# DC_Power_Regulation.net
KiCad netlist of a schematic drawn in Altium Designer
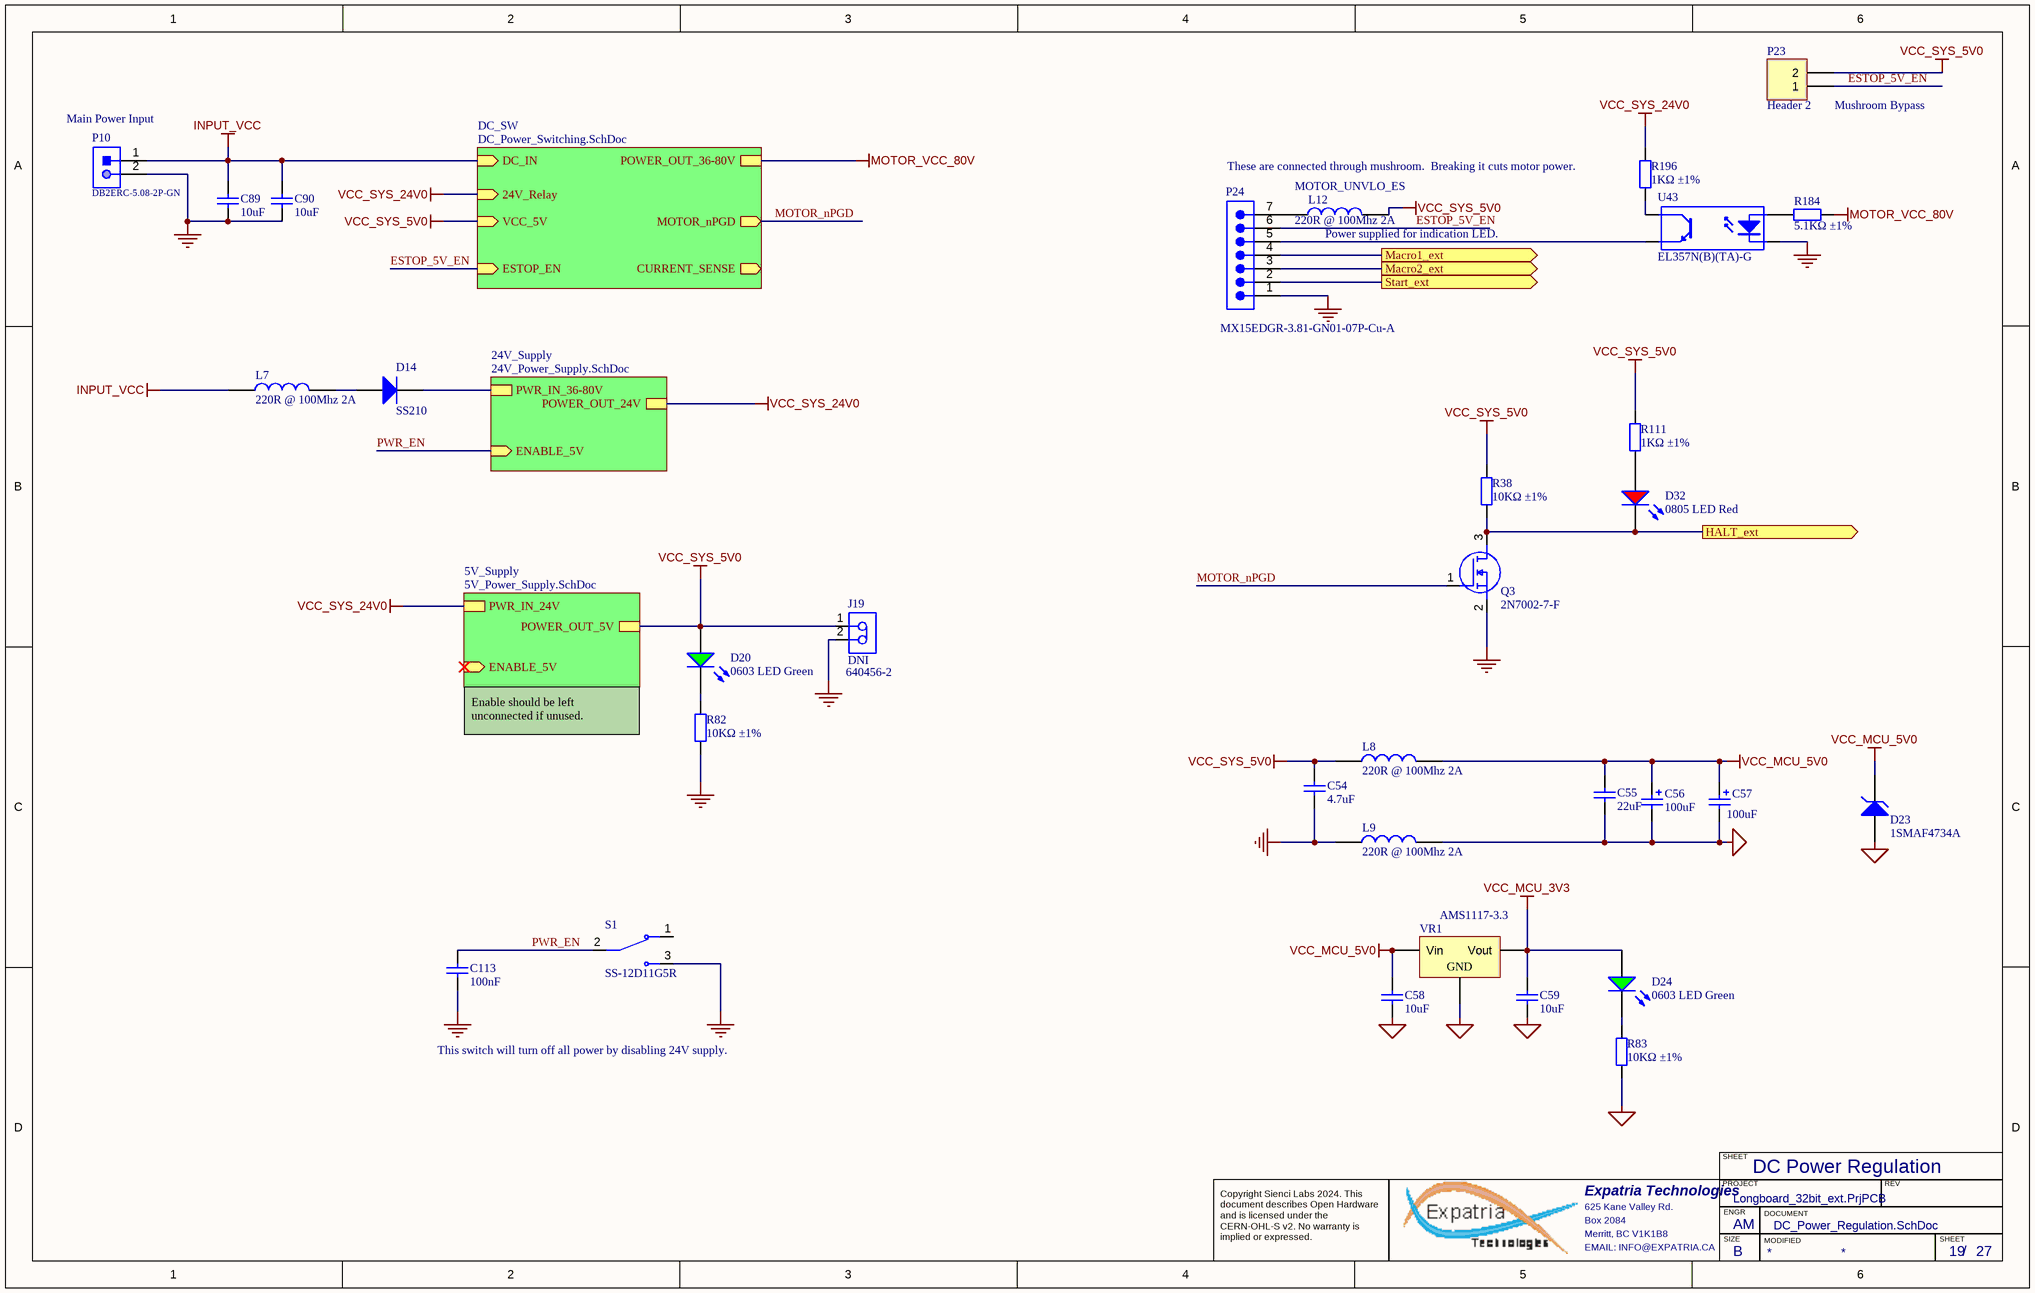
[diagram p0: DC_Power_Regulation.SchDoc]

(export (version "E")
  (design (tool "Eeschema 10.0.6"))
  (components
    (comp (ref "C54")
      (value "4.7uF")
      (footprint "0603_C")
      (description "16V 4.7uF X5R ±10% 0603 Multilayer Ceramic Capacitors MLCC - SMD/SMT ROHS")
      (fields (field (name "MANUFACTURER") "Samsung Electro-Mechanics") (field (name "TOLERANCE") "10%"))
      (libsource (lib "Sienci_Labs") (part "0603 4.7uF (475) 10% 16V"))
    )
    (comp (ref "C55")
      (value "22uF")
      (footprint "0805_C")
      (description "25V 22uF X5R ±20% 0805 Multilayer Ceramic Capacitors MLCC - SMD/SMT ROHS")
      (fields (field (name "MANUFACTURER") "Samsung Electro-Mechanics") (field (name "TOLERANCE") "20%"))
      (libsource (lib "Sienci_Labs") (part "0805 22uF (226) 20% 25V"))
    )
    (comp (ref "C56")
      (value "100uF")
      (footprint "CASE-B_3528")
      (description "Tantalum capacitor")
      (fields (field (name "MANUFACTURER") "AVX") (field (name "MANUFACTURER PART NUMBER") "TAJB107K006RNJ"))
      (libsource (lib "Cap") (part "3528 100uF (107) 10% 6.3V"))
    )
    (comp (ref "C57")
      (value "100uF")
      (footprint "WCAP-ASLI_D6.3H7.7")
      (fields
        (field (name "MANUFACTURER") "Capxon International Elec")
        (field (name "MANUFACTURER PART NUMBER") "HV101M035E077ETR")
      )
      (libsource (lib "IQAnalog") (part "865080445010"))
    )
    (comp (ref "C58")
      (value "10uF")
      (footprint "1206_C")
      (description "50V 10uF X5R ±10% 1206 Multilayer Ceramic Capacitors MLCC - SMD/SMT ROHS")
      (fields
        (field (name "MANUFACTURER") "Samsung Electro-Mechanics")
        (field (name "MANUFACTURER PART NUMBER") "CL31A106KBHNNNE")
      )
      (libsource (lib "Sienci_Labs") (part "1206 10uF (106) 10% 50V"))
    )
    (comp (ref "C59")
      (value "10uF")
      (footprint "1206_C")
      (description "50V 10uF X5R ±10% 1206 Multilayer Ceramic Capacitors MLCC - SMD/SMT ROHS")
      (fields
        (field (name "MANUFACTURER") "Samsung Electro-Mechanics")
        (field (name "MANUFACTURER PART NUMBER") "CL31A106KBHNNNE")
      )
      (libsource (lib "Sienci_Labs") (part "1206 10uF (106) 10% 50V"))
    )
    (comp (ref "C89")
      (value "10uF")
      (footprint "1206_C")
      (description "50V 10uF X5R ±10% 1206 Multilayer Ceramic Capacitors MLCC - SMD/SMT ROHS")
      (fields (field (name "MANUFACTURER") "Samsung Electro-Mechanics") (field (name "TOLERANCE") "10%"))
      (libsource (lib "Sienci_Labs") (part "1206 10uF (106) 10% 50V"))
    )
    (comp (ref "C90")
      (value "10uF")
      (footprint "1206_C")
      (description "50V 10uF X5R ±10% 1206 Multilayer Ceramic Capacitors MLCC - SMD/SMT ROHS")
      (fields (field (name "MANUFACTURER") "Samsung Electro-Mechanics") (field (name "TOLERANCE") "10%"))
      (libsource (lib "Sienci_Labs") (part "1206 10uF (106) 10% 50V"))
    )
    (comp (ref "C113")
      (value "100nF")
      (footprint "0603_C")
      (description "50V 100nF X7R ±10% 0603 Multilayer Ceramic Capacitors MLCC - SMD/SMT ROHS")
      (fields (field (name "MANUFACTURER") "YAGEO") (field (name "TOLERANCE") "10%"))
      (libsource (lib "Sienci_Labs") (part "0603 100nF (104) 10% 50V"))
    )
    (comp (ref "D14")
      (value "SS210")
      (footprint "SMA(DO-214AC)_S1")
      (description "100V 2A 850mV @ 2A SMA(DO-214AC) Schottky Barrier Diodes (SBD) ROHS")
      (fields (field (name "MANUFACTURER") "MDD(Microdiode Electronics)"))
      (libsource (lib "Diode") (part "SMA(DO-214AC) SS210"))
    )
    (comp (ref "D20")
      (value "0603 LED Green")
      (footprint "0603_LED_S1 - GREEN")
      (description "20mA -40℃~+85℃ 515nm~530nm Emerald 120° 60mW 0603 Light Emitting Diodes (LED) ROHS")
      (fields (field (name "MANUFACTURER PART NUMBER") "MHT192UGCT") (field (name "MANUFACTURER") "MEIHUA"))
      (libsource (lib "Sienci_Labs") (part "MHT192UGCT"))
    )
    (comp (ref "D23")
      (value "1SMAF4734A")
      (footprint "DIOM5226X240N")
      (description "27V ±5% 1W 500nA @ 20.5V SMA(DO-214AC) Zener Diodes RoHS")
      (fields (field (name "MANUFACTURER") "Shandong Jingdao Microelectronics"))
      (libsource (lib "PrintNC_GRBLHAL_Breakout") (part "BZT52C27"))
    )
    (comp (ref "D24")
      (value "0603 LED Green")
      (footprint "0603_LED_S1 - GREEN")
      (description "20mA -40℃~+85℃ 515nm~530nm Emerald 120° 60mW 0603 Light Emitting Diodes (LED) ROHS")
      (fields (field (name "MANUFACTURER PART NUMBER") "MHT192UGCT") (field (name "MANUFACTURER") "MEIHUA"))
      (libsource (lib "Sienci_Labs") (part "MHT192UGCT"))
    )
    (comp (ref "D32")
      (value "0805 LED Red")
      (footprint "0805_LED_S1 - RED")
      (description "Red 0805 Light Emitting Diodes (LED) ROHS")
      (fields
        (field (name "MANUFACTURER") "Foshan NationStar Optoelectronics")
        (field (name "MANUFACTURER PART NUMBER") "NCD0805R1")
      )
      (libsource (lib "Sienci_Labs") (part "0805 LED Red"))
    )
    (comp (ref "J19")
      (value "DNI")
      (footprint "TECO-640456-2_V")
      (fields (field (name "MANUFACTURER") "TE Connectivity") (field (name "ALTIUM_VALUE") "640456-2"))
      (libsource (lib "Altium Content Vault") (part "CN-2P-F-QF2"))
    )
    (comp (ref "L7")
      (value "220R @ 100Mhz 2A")
      (footprint "0805_R")
      (description "150mΩ ±25% 220Ω@100MHz 0805 Ferrite Beads ROHS")
      (fields
        (field (name "MANUFACTURER PART NUMBER") "CBW201209U221T")
        (field (name "MANUFACTURER") "FH (Guangdong Fenghua Advanced Tech)")
      )
      (libsource (lib "Sienci_Labs") (part "CBW201209U221T"))
    )
    (comp (ref "L8")
      (value "220R @ 100Mhz 2A")
      (footprint "0805_R")
      (description "150mΩ ±25% 220Ω@100MHz 0805 Ferrite Beads ROHS")
      (fields
        (field (name "MANUFACTURER PART NUMBER") "CBW201209U221T")
        (field (name "MANUFACTURER") "FH (Guangdong Fenghua Advanced Tech)")
      )
      (libsource (lib "Sienci_Labs") (part "CBW201209U221T"))
    )
    (comp (ref "L9")
      (value "220R @ 100Mhz 2A")
      (footprint "0805_R")
      (description "150mΩ ±25% 220Ω@100MHz 0805 Ferrite Beads ROHS")
      (fields
        (field (name "MANUFACTURER PART NUMBER") "CBW201209U221T")
        (field (name "MANUFACTURER") "FH (Guangdong Fenghua Advanced Tech)")
      )
      (libsource (lib "Sienci_Labs") (part "CBW201209U221T"))
    )
    (comp (ref "L12")
      (value "220R @ 100Mhz 2A")
      (footprint "0805_R")
      (description "150mΩ ±25% 220Ω@100MHz 0805 Ferrite Beads ROHS")
      (fields
        (field (name "MANUFACTURER PART NUMBER") "CBW201209U221T")
        (field (name "MANUFACTURER") "FH (Guangdong Fenghua Advanced Tech)")
      )
      (libsource (lib "Sienci_Labs") (part "CBW201209U221T"))
    )
    (comp (ref "P10")
      (value "DB2ERC-5.08-2P-GN")
      (footprint "CONN-TH_2P-P5.08_DB2ERC-5.08-2P")
      (fields (field (name "MANUFACTURER") "Dibo"))
      (libsource (lib "Sienci_Labs") (part "DB2ERC-5.08-2P-GN"))
    )
    (comp (ref "P23")
      (value "Header 2")
      (footprint "HDR1X2")
      (description "Straight Square Pins 2 2.54mm Black Brass 1x2P Plugin,P=2.54mm Pin Headers ROHS")
      (fields
        (field (name "MANUFACTURER") "MOLEX")
        (field (name "MANUFACTURER PART NUMBER") "22284020")
        (field (name "PUBLISHER") "Altium Limited")
      )
      (libsource (lib "Sienci_Labs") (part "Header 2"))
    )
    (comp (ref "P24")
      (value "MX15EDGR-3.81-GN01-07P-Cu-A")
      (footprint "691322310007")
      (fields (field (name "MANUFACTURER") "MAX"))
      (libsource (lib "Sienci_Labs") (part "MX15EDGR-3.81-GN01-07P-Cu-A"))
    )
    (comp (ref "Q3")
      (value "2N7002-7-F")
      (footprint "SOT-23(SOT-23-3)")
      (description "60V 115mA 7.5Ω@5V,50mA 370mW N Channel SOT-23 MOSFETs ROHS")
      (fields (field (name "MANUFACTURER") "Diodes Inc.") (field (name "MOUSER PART NUMBER") "621-2N7002-F"))
      (libsource (lib "Sienci_Labs") (part "2N7002-7-F"))
    )
    (comp (ref "R38")
      (value "10KΩ ±1%")
      (footprint "0603_R")
      (description "Chip resistor")
      (fields (field (name "MANUFACTURER") "Uniroyal Elec") (field (name "POWER") "1/10W"))
      (libsource (lib "Sienci_Labs") (part "0603 10K (1002) 1%"))
    )
    (comp (ref "R82")
      (value "10KΩ ±1%")
      (footprint "0603_R")
      (description "Chip resistor")
      (fields (field (name "MANUFACTURER") "Uniroyal Elec") (field (name "POWER") "1/10W"))
      (libsource (lib "Sienci_Labs") (part "0603 10K (1002) 1%"))
    )
    (comp (ref "R83")
      (value "10KΩ ±1%")
      (footprint "0603_R")
      (description "Chip resistor")
      (fields (field (name "MANUFACTURER") "Uniroyal Elec") (field (name "POWER") "1/10W"))
      (libsource (lib "Sienci_Labs") (part "0603 10K (1002) 1%"))
    )
    (comp (ref "R111")
      (value "1KΩ ±1%")
      (footprint "0603_R")
      (description "Chip resistor")
      (fields (field (name "MANUFACTURER") "Uniroyal Elec") (field (name "POWER") "1/10W"))
      (libsource (lib "Sienci_Labs") (part "0603 1K (1001) 1%"))
    )
    (comp (ref "R184")
      (value "5.1KΩ ±1%")
      (footprint "0603_R")
      (description "Chip resistor")
      (fields
        (field (name "MANUFACTURER") "Uniroyal Elec")
        (field (name "MANUFACTURER PART NUMBER") "0603WAF5101T5E")
      )
      (libsource (lib "RES") (part "0603 5.1K (5101) 1%"))
    )
    (comp (ref "R196")
      (value "1KΩ ±1%")
      (footprint "0603_R")
      (description "Chip resistor")
      (fields (field (name "MANUFACTURER") "Uniroyal Elec") (field (name "POWER") "1/10W"))
      (libsource (lib "Sienci_Labs") (part "0603 1K (1001) 1%"))
    )
    (comp (ref "S1")
      (value "SS-12D11G5R")
      (footprint "SW_500SSP1S1M6QEA")
      (description "Shrouded 5A SPDT 125V 125V 5A 10000次 Black Plugin Slide Switches ROHS")
      (fields (field (name "MANUFACTURER") "XKB Connectivity"))
      (libsource (lib "Sienci_Labs") (part "SS-12D11G5R"))
    )
    (comp (ref "U43")
      (value "EL357N(B)(TA)-G")
      (footprint "Miscellaneous Devices LC:SOP-4_P2.54")
      (description "Optocoupler SOP-4, EL357N(B)(TA)-G, Everlight Electronics")
      (fields (field (name "MANUFACTURER") "Everlight"))
      (libsource (lib "Sienci_Labs") (part "EL357N(B)(TA)-G_[C6649]"))
    )
    (comp (ref "VR1")
      (value "AMS1117-3.3")
      (footprint "SOT-223")
      (description "Vout=3.3V 1A 72dB@(120Hz) (LDO)")
      (fields (field (name "MANUFACTURER") "AMS"))
      (libsource (lib "LDO") (part "SOT-223 AMS1117-3.3"))
    )
  )
  (nets
    (net (code "3") (name "/ESTOP_5V_EN") (class "Default")
      (node (ref "P23") (pin "1") (pinfunction "1_1") (pintype "passive"))
      (node (ref "P24") (pin "6") (pinfunction "6_6") (pintype "passive"))
    )
    (net (code "4") (name "/HALT_ext") (class "Default")
      (node (ref "D32") (pin "K") (pinfunction "K_K") (pintype "passive"))
      (node (ref "Q3") (pin "3") (pinfunction "D_3") (pintype "passive"))
      (node (ref "R38") (pin "1") (pinfunction "1_1") (pintype "passive"))
    )
    (net (code "5") (name "/MOTOR_nPGD") (class "Default")
      (node (ref "Q3") (pin "1") (pinfunction "G_1") (pintype "passive"))
    )
    (net (code "6") (name "/Macro1_ext") (class "Default")
      (node (ref "P24") (pin "4") (pinfunction "4_4") (pintype "passive"))
    )
    (net (code "7") (name "/Macro2_ext") (class "Default")
      (node (ref "P24") (pin "3") (pinfunction "3_3") (pintype "passive"))
    )
    (net (code "8") (name "/PWR_EN") (class "Default")
      (node (ref "C113") (pin "2") (pinfunction "2_2") (pintype "passive"))
      (node (ref "S1") (pin "2") (pinfunction "COM_2") (pintype "passive"))
    )
    (net (code "9") (name "/PWR_IN_36-80V") (class "Default")
      (node (ref "D14") (pin "2") (pinfunction "K_2") (pintype "passive"))
    )
    (net (code "10") (name "/Start_ext") (class "Default")
      (node (ref "P24") (pin "2") (pinfunction "2_2") (pintype "passive"))
    )
    (net (code "11") (name "GND") (class "Default")
      (node (ref "C113") (pin "1") (pinfunction "1_1") (pintype "passive"))
      (node (ref "C54") (pin "1") (pinfunction "1_1") (pintype "passive"))
      (node (ref "C89") (pin "1") (pinfunction "1_1") (pintype "passive"))
      (node (ref "C90") (pin "1") (pinfunction "1_1") (pintype "passive"))
      (node (ref "J19") (pin "2") (pinfunction "2_2") (pintype "passive"))
      (node (ref "L9") (pin "1") (pinfunction "1_1") (pintype "passive"))
      (node (ref "P10") (pin "2") (pinfunction "2_2") (pintype "passive"))
      (node (ref "P24") (pin "1") (pinfunction "1_1") (pintype "passive"))
      (node (ref "Q3") (pin "2") (pinfunction "S_2") (pintype "passive"))
      (node (ref "R82") (pin "1") (pinfunction "1_1") (pintype "passive"))
      (node (ref "S1") (pin "3") (pinfunction "NO_3") (pintype "passive"))
      (node (ref "U43") (pin "2") (pinfunction "K_2") (pintype "passive"))
    )
    (net (code "12") (name "INPUT_VCC") (class "Default")
      (node (ref "C89") (pin "2") (pinfunction "2_2") (pintype "passive"))
      (node (ref "C90") (pin "2") (pinfunction "2_2") (pintype "passive"))
      (node (ref "L7") (pin "1") (pinfunction "1_1") (pintype "passive"))
      (node (ref "P10") (pin "1") (pinfunction "1_1") (pintype "passive"))
    )
    (net (code "13") (name "MCU_GND") (class "Default")
      (node (ref "C55") (pin "1") (pinfunction "1_1") (pintype "passive"))
      (node (ref "C56") (pin "2") (pinfunction "2_2") (pintype "passive"))
      (node (ref "C57") (pin "2") (pinfunction "N_2") (pintype "passive"))
      (node (ref "C58") (pin "1") (pinfunction "1_1") (pintype "passive"))
      (node (ref "C59") (pin "1") (pinfunction "1_1") (pintype "passive"))
      (node (ref "D23") (pin "1") (pinfunction "A_1") (pintype "passive"))
      (node (ref "L9") (pin "2") (pinfunction "2_2") (pintype "passive"))
      (node (ref "R83") (pin "1") (pinfunction "1_1") (pintype "passive"))
      (node (ref "VR1") (pin "1") (pinfunction "GND_1") (pintype "passive"))
    )
    (net (code "14") (name "MOTOR_VCC_80V") (class "Default")
      (node (ref "R184") (pin "2") (pinfunction "2_2") (pintype "passive"))
    )
    (net (code "15") (name "Net-(D14-A)") (class "Default")
      (node (ref "D14") (pin "1") (pinfunction "A_1") (pintype "passive"))
      (node (ref "L7") (pin "2") (pinfunction "2_2") (pintype "passive"))
    )
    (net (code "16") (name "Net-(D20-PadK)") (class "Default")
      (node (ref "D20") (pin "K") (pinfunction "K_K") (pintype "passive"))
      (node (ref "R82") (pin "2") (pinfunction "2_2") (pintype "passive"))
    )
    (net (code "17") (name "Net-(D24-PadK)") (class "Default")
      (node (ref "D24") (pin "K") (pinfunction "K_K") (pintype "passive"))
      (node (ref "R83") (pin "2") (pinfunction "2_2") (pintype "passive"))
    )
    (net (code "18") (name "Net-(D32-PadA)") (class "Default")
      (node (ref "D32") (pin "A") (pinfunction "A_A") (pintype "passive"))
      (node (ref "R111") (pin "1") (pinfunction "1_1") (pintype "passive"))
    )
    (net (code "19") (name "Net-(L12-Pad1)") (class "Default")
      (node (ref "L12") (pin "1") (pinfunction "1_1") (pintype "passive"))
      (node (ref "P24") (pin "7") (pinfunction "7_7") (pintype "passive"))
    )
    (net (code "20") (name "Net-(U43-A)") (class "Default")
      (node (ref "R184") (pin "1") (pinfunction "1_1") (pintype "passive"))
      (node (ref "U43") (pin "1") (pinfunction "A_1") (pintype "passive"))
    )
    (net (code "21") (name "Net-(U43-C)") (class "Default")
      (node (ref "R196") (pin "1") (pinfunction "1_1") (pintype "passive"))
      (node (ref "U43") (pin "4") (pinfunction "C_4") (pintype "passive"))
    )
    (net (code "22") (name "Net-(U43-E)") (class "Default")
      (node (ref "P24") (pin "5") (pinfunction "5_5") (pintype "passive"))
      (node (ref "U43") (pin "3") (pinfunction "E_3") (pintype "passive"))
    )
    (net (code "23") (name "VCC_MCU_3V3") (class "Default")
      (node (ref "C59") (pin "2") (pinfunction "2_2") (pintype "passive"))
      (node (ref "D24") (pin "A") (pinfunction "A_A") (pintype "passive"))
      (node (ref "VR1") (pin "2") (pinfunction "Vout_2") (pintype "passive"))
    )
    (net (code "24") (name "VCC_MCU_5V0") (class "Default")
      (node (ref "C55") (pin "2") (pinfunction "2_2") (pintype "passive"))
      (node (ref "C56") (pin "1") (pinfunction "1_1") (pintype "passive"))
      (node (ref "C57") (pin "1") (pinfunction "P_1") (pintype "passive"))
      (node (ref "C58") (pin "2") (pinfunction "2_2") (pintype "passive"))
      (node (ref "D23") (pin "2") (pinfunction "K_2") (pintype "passive"))
      (node (ref "L8") (pin "2") (pinfunction "2_2") (pintype "passive"))
      (node (ref "VR1") (pin "3") (pinfunction "Vin_3") (pintype "passive"))
    )
    (net (code "25") (name "VCC_SYS_5V0") (class "Default")
      (node (ref "C54") (pin "2") (pinfunction "2_2") (pintype "passive"))
      (node (ref "D20") (pin "A") (pinfunction "A_A") (pintype "passive"))
      (node (ref "J19") (pin "1") (pinfunction "1_1") (pintype "passive"))
      (node (ref "L12") (pin "2") (pinfunction "2_2") (pintype "passive"))
      (node (ref "L8") (pin "1") (pinfunction "1_1") (pintype "passive"))
      (node (ref "P23") (pin "2") (pinfunction "2_2") (pintype "passive"))
      (node (ref "R111") (pin "2") (pinfunction "2_2") (pintype "passive"))
      (node (ref "R38") (pin "2") (pinfunction "2_2") (pintype "passive"))
    )
    (net (code "26") (name "VCC_SYS_24V0") (class "Default")
      (node (ref "R196") (pin "2") (pinfunction "2_2") (pintype "passive"))
    )
    (net (code "27") (name "unconnected-(S1-NC-Pad1)") (class "Default")
      (node (ref "S1") (pin "1") (pinfunction "NC_1") (pintype "passive"))
    )
  )
)
